# X7A15T-Fabric.net
KiCad netlist of a schematic drawn in Altium Designer
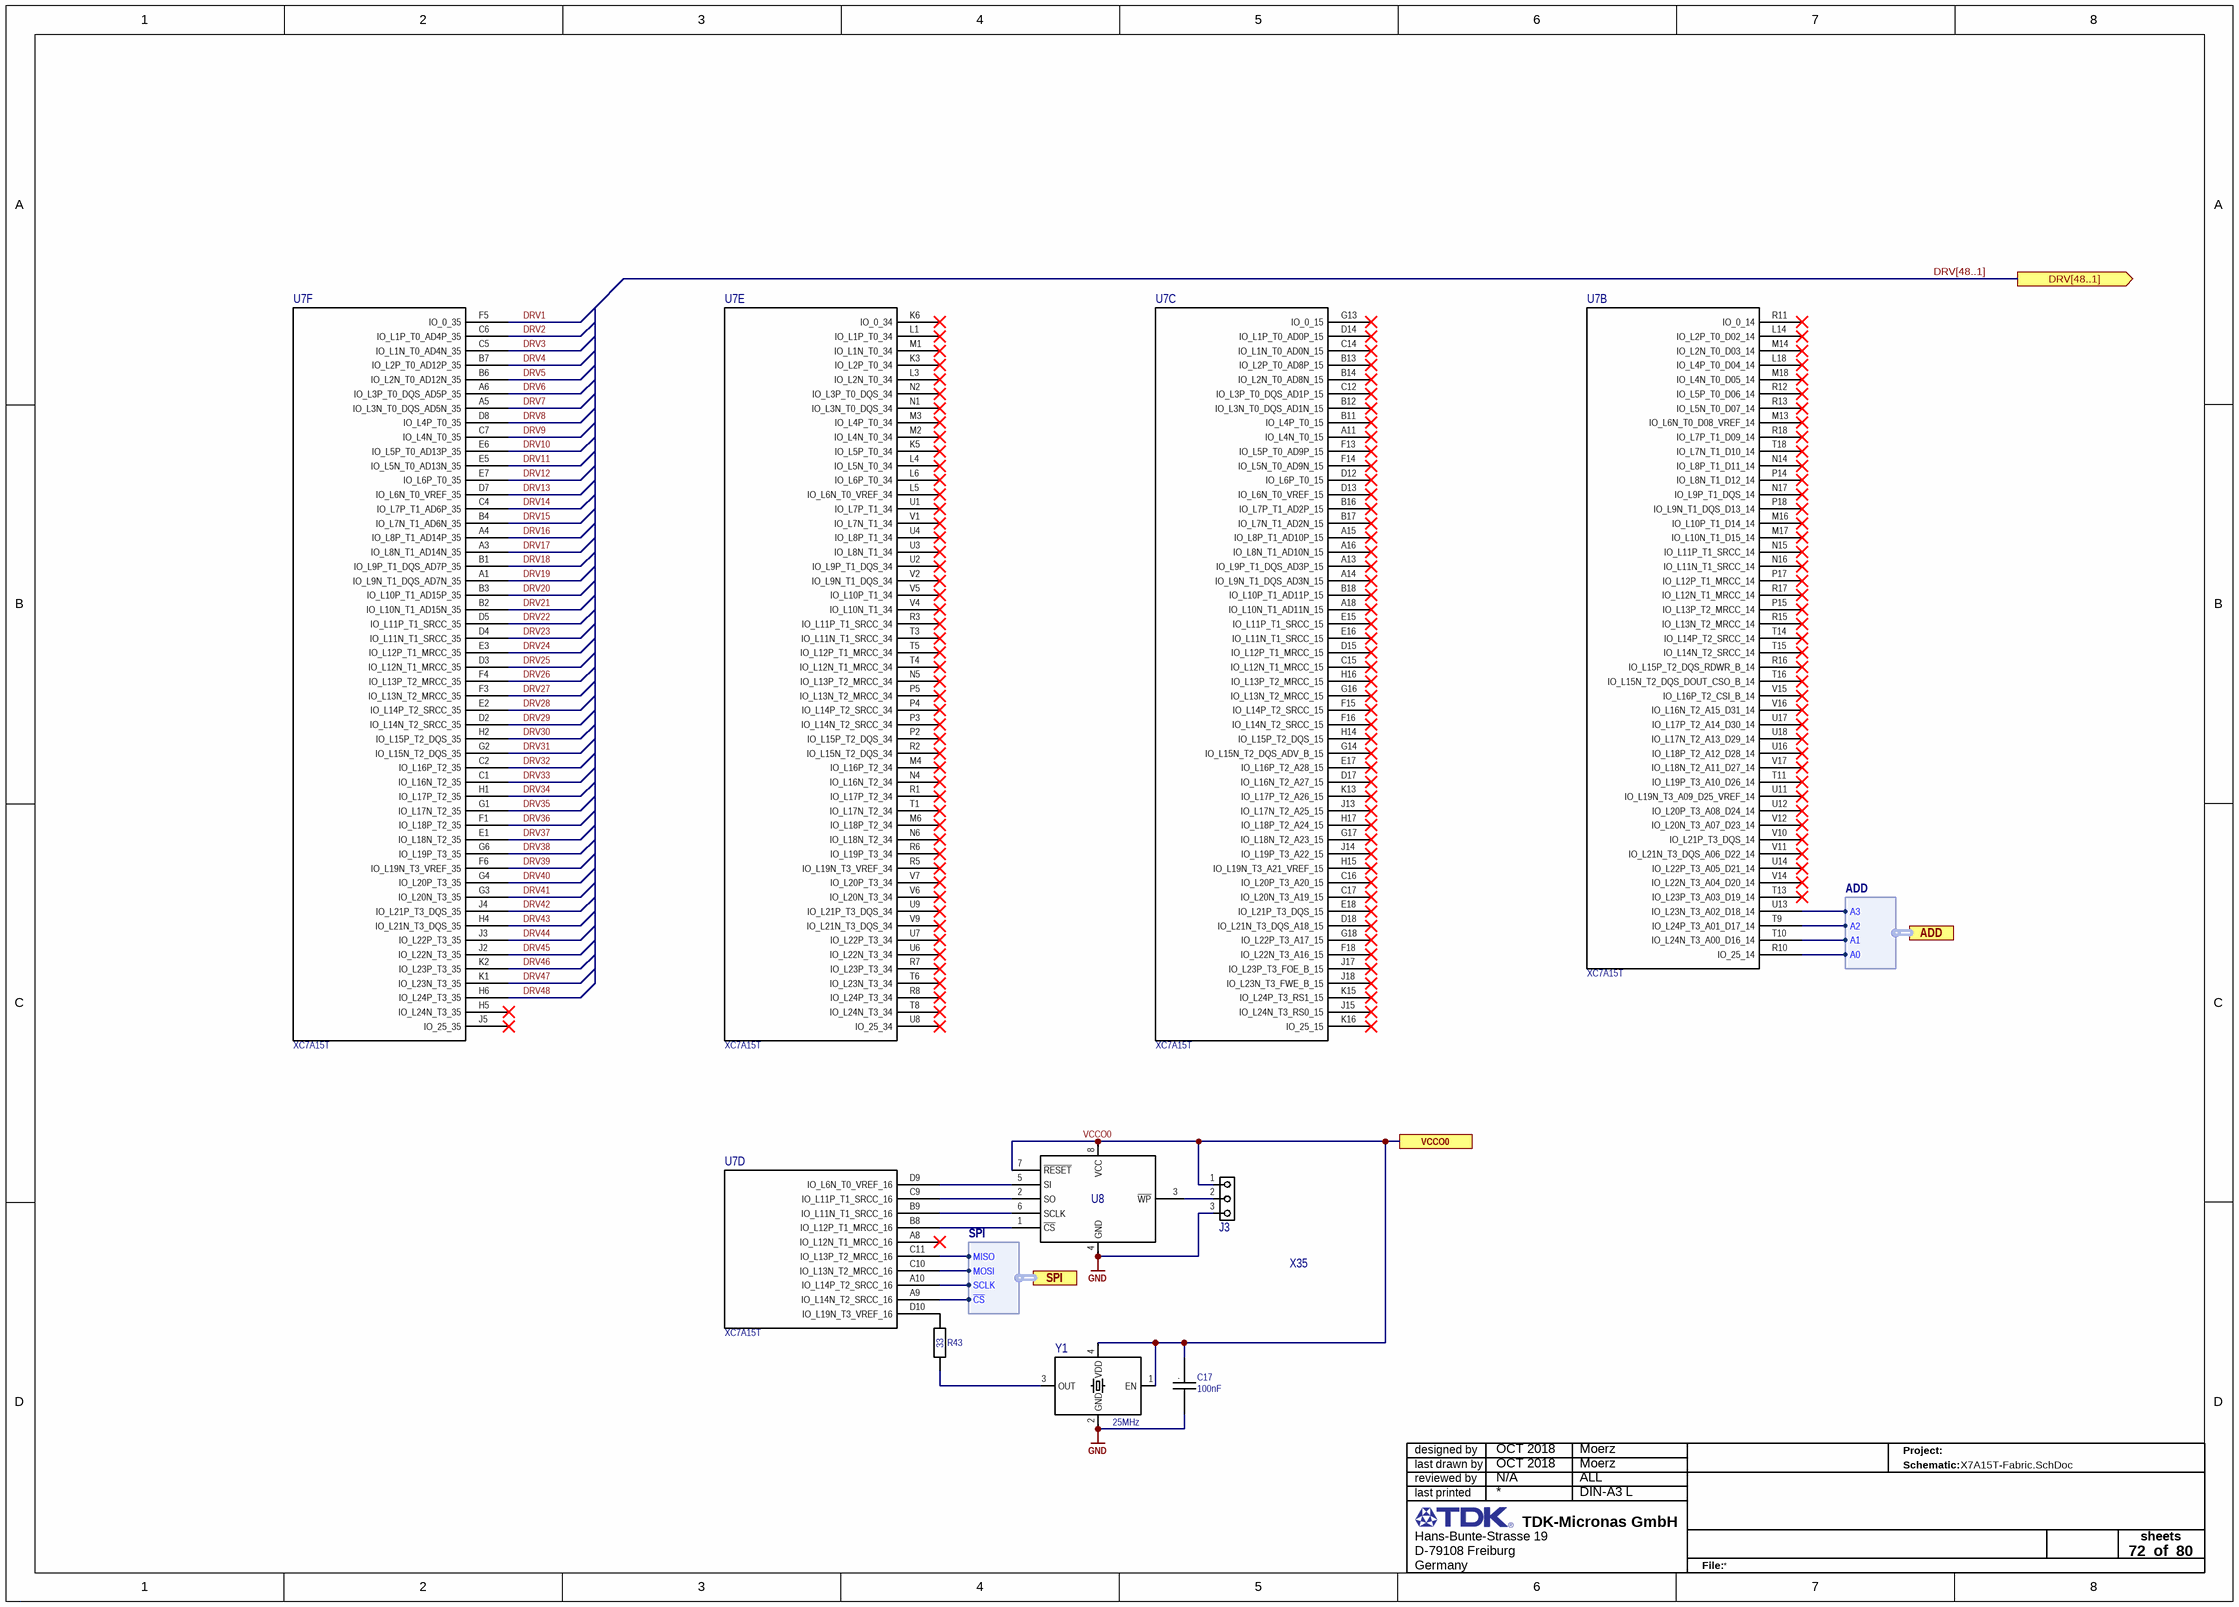
[diagram p0: X7A15T-Fabric.SchDoc]

(export (version "E")
  (design (tool "Eeschema 10.0.6"))
  (components
    (comp (ref "C17")
      (value "100nF")
      (footprint "C0402 Reflow")
      (description "CAP CER 0.1UF 16V X7R 0402")
      (fields
        (field (name "TOLERANCE") "±5%")
        (field (name "02. DISTRIBUTOR PART NUMBER") "399-7761-6-ND")
        (field (name "13. CREATED DATE/NAME") "AUG2018/Hören")
      )
      (libsource (lib "chickenfood") (part "C"))
    )
    (comp (ref "J3")
      (value "J")
      (footprint "Header 100mil 3x1")
      (description "CONN HEADER VERT 3POS 2.54MM")
      (fields
        (field (name "02. DISTRIBUTOR PART NUMBER") "HMTSW-103-07-G-S-240")
        (field (name "13. CREATED DATE/NAME") "AUG2018/Hören")
      )
      (libsource (lib "chickenfood") (part "Header 3Pins 100mil"))
    )
    (comp (ref "R43")
      (value "33")
      (footprint "R0402 Reflow")
      (description "RES SMD 33 OHM 1% 1/16W 0402")
      (fields
        (field (name "TOLERANCE") "±1%")
        (field (name "02. DISTRIBUTOR PART NUMBER") "311-33.0LRDKR-ND")
        (field (name "13. CREATED DATE/NAME") "AUG2018/Hören")
      )
      (libsource (lib "chickenfood") (part "R"))
    )
    (comp (ref "U7")
      (value "U")
      (footprint "XC7A15T-1CSG324C")
      (description "XC7A15T-1CSG324C")
      (fields (field (name "MFR") "XILINX") (field (name "NICNAME") "XC7A15T"))
      (libsource (lib "tom") (part "XC7A15T-CS324"))
    )
    (comp (ref "U8")
      (value "U")
      (footprint "SOIC8 (R-8)")
      (description "IC FLASH 32M SPI 80MHZ 8SOP")
      (fields (field (name "13. CREATED DATE/NAME") "AUG 2018 / Hören"))
      (libsource (lib "tom") (part "MX25R3235FM1IH0"))
    )
    (comp (ref "X35")
      (value "X")
      (description "CONN JUMPER SHORTING .100\" GOLD")
      (fields
        (field (name "02. DISTRIBUTOR PART NUMBER") "S9337-ND")
        (field (name "07. MANUFACTURER  PART NUMBER") "QPC02SXGN-RC")
        (field (name "13. CREATED DATE/NAME") "AUG2018/Hören")
      )
      (libsource (lib "chickenfood") (part "Jumper"))
    )
    (comp (ref "Y1")
      (value "Y")
      (footprint "4SMD")
      (description "XTAL OSC XO 25.0000MHZ CMOS SMD")
      (fields
        (field (name "02. DISTRIBUTOR PART NUMBER") "535-9568-1-ND")
        (field (name "07. MANUFACTURER  PART NUMBER") "ASE-25.000MHZ-LC-T")
        (field (name "FREQUENCY") "25MHz")
        (field (name "13. CREATED DATE/NAME") "AUG 2018 / Hören")
      )
      (libsource (lib "tom") (part "ASE-25.000MHZ-LC-T"))
    )
  )
  (nets
    (net (code "3") (name "/A0") (class "Default")
      (node (ref "U7") (pin "R10") (pinfunction "IO_25_14_R10") (pintype "passive"))
    )
    (net (code "4") (name "/A1") (class "Default")
      (node (ref "U7") (pin "T10") (pinfunction "IO_L24N_T3_A00_D16_14_T10") (pintype "passive"))
    )
    (net (code "5") (name "/A2") (class "Default")
      (node (ref "U7") (pin "T9") (pinfunction "IO_L24P_T3_A01_D17_14_T9") (pintype "passive"))
    )
    (net (code "6") (name "/A3") (class "Default")
      (node (ref "U7") (pin "U13") (pinfunction "IO_L23N_T3_A02_D18_14_U13") (pintype "passive"))
    )
    (net (code "7") (name "/DRV1") (class "Default")
      (node (ref "U7") (pin "F5") (pinfunction "IO_0_35_F5") (pintype "passive"))
    )
    (net (code "8") (name "/DRV2") (class "Default")
      (node (ref "U7") (pin "C6") (pinfunction "IO_L1P_T0_AD4P_35_C6") (pintype "passive"))
    )
    (net (code "9") (name "/DRV3") (class "Default")
      (node (ref "U7") (pin "C5") (pinfunction "IO_L1N_T0_AD4N_35_C5") (pintype "passive"))
    )
    (net (code "10") (name "/DRV4") (class "Default")
      (node (ref "U7") (pin "B7") (pinfunction "IO_L2P_T0_AD12P_35_B7") (pintype "passive"))
    )
    (net (code "11") (name "/DRV5") (class "Default")
      (node (ref "U7") (pin "B6") (pinfunction "IO_L2N_T0_AD12N_35_B6") (pintype "passive"))
    )
    (net (code "12") (name "/DRV6") (class "Default")
      (node (ref "U7") (pin "A6") (pinfunction "IO_L3P_T0_DQS_AD5P_35_A6") (pintype "passive"))
    )
    (net (code "13") (name "/DRV7") (class "Default")
      (node (ref "U7") (pin "A5") (pinfunction "IO_L3N_T0_DQS_AD5N_35_A5") (pintype "passive"))
    )
    (net (code "14") (name "/DRV8") (class "Default")
      (node (ref "U7") (pin "D8") (pinfunction "IO_L4P_T0_35_D8") (pintype "passive"))
    )
    (net (code "15") (name "/DRV9") (class "Default")
      (node (ref "U7") (pin "C7") (pinfunction "IO_L4N_T0_35_C7") (pintype "passive"))
    )
    (net (code "16") (name "/DRV10") (class "Default")
      (node (ref "U7") (pin "E6") (pinfunction "IO_L5P_T0_AD13P_35_E6") (pintype "passive"))
    )
    (net (code "17") (name "/DRV11") (class "Default")
      (node (ref "U7") (pin "E5") (pinfunction "IO_L5N_T0_AD13N_35_E5") (pintype "passive"))
    )
    (net (code "18") (name "/DRV12") (class "Default")
      (node (ref "U7") (pin "E7") (pinfunction "IO_L6P_T0_35_E7") (pintype "passive"))
    )
    (net (code "19") (name "/DRV13") (class "Default")
      (node (ref "U7") (pin "D7") (pinfunction "IO_L6N_T0_VREF_35_D7") (pintype "passive"))
    )
    (net (code "20") (name "/DRV14") (class "Default")
      (node (ref "U7") (pin "C4") (pinfunction "IO_L7P_T1_AD6P_35_C4") (pintype "passive"))
    )
    (net (code "21") (name "/DRV15") (class "Default")
      (node (ref "U7") (pin "B4") (pinfunction "IO_L7N_T1_AD6N_35_B4") (pintype "passive"))
    )
    (net (code "22") (name "/DRV16") (class "Default")
      (node (ref "U7") (pin "A4") (pinfunction "IO_L8P_T1_AD14P_35_A4") (pintype "passive"))
    )
    (net (code "23") (name "/DRV17") (class "Default")
      (node (ref "U7") (pin "A3") (pinfunction "IO_L8N_T1_AD14N_35_A3") (pintype "passive"))
    )
    (net (code "24") (name "/DRV18") (class "Default")
      (node (ref "U7") (pin "B1") (pinfunction "IO_L9P_T1_DQS_AD7P_35_B1") (pintype "passive"))
    )
    (net (code "25") (name "/DRV19") (class "Default")
      (node (ref "U7") (pin "A1") (pinfunction "IO_L9N_T1_DQS_AD7N_35_A1") (pintype "passive"))
    )
    (net (code "26") (name "/DRV20") (class "Default")
      (node (ref "U7") (pin "B3") (pinfunction "IO_L10P_T1_AD15P_35_B3") (pintype "passive"))
    )
    (net (code "27") (name "/DRV21") (class "Default")
      (node (ref "U7") (pin "B2") (pinfunction "IO_L10N_T1_AD15N_35_B2") (pintype "passive"))
    )
    (net (code "28") (name "/DRV22") (class "Default")
      (node (ref "U7") (pin "D5") (pinfunction "IO_L11P_T1_SRCC_35_D5") (pintype "passive"))
    )
    (net (code "29") (name "/DRV23") (class "Default")
      (node (ref "U7") (pin "D4") (pinfunction "IO_L11N_T1_SRCC_35_D4") (pintype "passive"))
    )
    (net (code "30") (name "/DRV24") (class "Default")
      (node (ref "U7") (pin "E3") (pinfunction "IO_L12P_T1_MRCC_35_E3") (pintype "passive"))
    )
    (net (code "31") (name "/DRV25") (class "Default")
      (node (ref "U7") (pin "D3") (pinfunction "IO_L12N_T1_MRCC_35_D3") (pintype "passive"))
    )
    (net (code "32") (name "/DRV26") (class "Default")
      (node (ref "U7") (pin "F4") (pinfunction "IO_L13P_T2_MRCC_35_F4") (pintype "passive"))
    )
    (net (code "33") (name "/DRV27") (class "Default")
      (node (ref "U7") (pin "F3") (pinfunction "IO_L13N_T2_MRCC_35_F3") (pintype "passive"))
    )
    (net (code "34") (name "/DRV28") (class "Default")
      (node (ref "U7") (pin "E2") (pinfunction "IO_L14P_T2_SRCC_35_E2") (pintype "passive"))
    )
    (net (code "35") (name "/DRV29") (class "Default")
      (node (ref "U7") (pin "D2") (pinfunction "IO_L14N_T2_SRCC_35_D2") (pintype "passive"))
    )
    (net (code "36") (name "/DRV30") (class "Default")
      (node (ref "U7") (pin "H2") (pinfunction "IO_L15P_T2_DQS_35_H2") (pintype "passive"))
    )
    (net (code "37") (name "/DRV31") (class "Default")
      (node (ref "U7") (pin "G2") (pinfunction "IO_L15N_T2_DQS_35_G2") (pintype "passive"))
    )
    (net (code "38") (name "/DRV32") (class "Default")
      (node (ref "U7") (pin "C2") (pinfunction "IO_L16P_T2_35_C2") (pintype "passive"))
    )
    (net (code "39") (name "/DRV33") (class "Default")
      (node (ref "U7") (pin "C1") (pinfunction "IO_L16N_T2_35_C1") (pintype "passive"))
    )
    (net (code "40") (name "/DRV34") (class "Default")
      (node (ref "U7") (pin "H1") (pinfunction "IO_L17P_T2_35_H1") (pintype "passive"))
    )
    (net (code "41") (name "/DRV35") (class "Default")
      (node (ref "U7") (pin "G1") (pinfunction "IO_L17N_T2_35_G1") (pintype "passive"))
    )
    (net (code "42") (name "/DRV36") (class "Default")
      (node (ref "U7") (pin "F1") (pinfunction "IO_L18P_T2_35_F1") (pintype "passive"))
    )
    (net (code "43") (name "/DRV37") (class "Default")
      (node (ref "U7") (pin "E1") (pinfunction "IO_L18N_T2_35_E1") (pintype "passive"))
    )
    (net (code "44") (name "/DRV38") (class "Default")
      (node (ref "U7") (pin "G6") (pinfunction "IO_L19P_T3_35_G6") (pintype "passive"))
    )
    (net (code "45") (name "/DRV39") (class "Default")
      (node (ref "U7") (pin "F6") (pinfunction "IO_L19N_T3_VREF_35_F6") (pintype "passive"))
    )
    (net (code "46") (name "/DRV40") (class "Default")
      (node (ref "U7") (pin "G4") (pinfunction "IO_L20P_T3_35_G4") (pintype "passive"))
    )
    (net (code "47") (name "/DRV41") (class "Default")
      (node (ref "U7") (pin "G3") (pinfunction "IO_L20N_T3_35_G3") (pintype "passive"))
    )
    (net (code "48") (name "/DRV42") (class "Default")
      (node (ref "U7") (pin "J4") (pinfunction "IO_L21P_T3_DQS_35_J4") (pintype "passive"))
    )
    (net (code "49") (name "/DRV43") (class "Default")
      (node (ref "U7") (pin "H4") (pinfunction "IO_L21N_T3_DQS_35_H4") (pintype "passive"))
    )
    (net (code "50") (name "/DRV44") (class "Default")
      (node (ref "U7") (pin "J3") (pinfunction "IO_L22P_T3_35_J3") (pintype "passive"))
    )
    (net (code "51") (name "/DRV45") (class "Default")
      (node (ref "U7") (pin "J2") (pinfunction "IO_L22N_T3_35_J2") (pintype "passive"))
    )
    (net (code "52") (name "/DRV46") (class "Default")
      (node (ref "U7") (pin "K2") (pinfunction "IO_L23P_T3_35_K2") (pintype "passive"))
    )
    (net (code "53") (name "/DRV47") (class "Default")
      (node (ref "U7") (pin "K1") (pinfunction "IO_L23N_T3_35_K1") (pintype "passive"))
    )
    (net (code "54") (name "/DRV48") (class "Default")
      (node (ref "U7") (pin "H6") (pinfunction "IO_L24P_T3_35_H6") (pintype "passive"))
    )
    (net (code "56") (name "/MISO") (class "Default")
      (node (ref "U7") (pin "C11") (pinfunction "IO_L13P_T2_MRCC_16_C11") (pintype "passive"))
    )
    (net (code "57") (name "/MOSI") (class "Default")
      (node (ref "U7") (pin "C10") (pinfunction "IO_L13N_T2_MRCC_16_C10") (pintype "passive"))
    )
    (net (code "58") (name "/SCLK") (class "Default")
      (node (ref "U7") (pin "A10") (pinfunction "IO_L14P_T2_SRCC_16_A10") (pintype "passive"))
    )
    (net (code "59") (name "/VCCO0") (class "Default")
      (node (ref "C17") (pin "1") (pinfunction "1_1") (pintype "passive"))
      (node (ref "J3") (pin "1") (pinfunction "1_1") (pintype "passive"))
      (node (ref "U8") (pin "7") (pinfunction "RESET_7") (pintype "passive"))
      (node (ref "U8") (pin "8") (pinfunction "VCC_8") (pintype "passive"))
      (node (ref "Y1") (pin "1") (pinfunction "EN_1") (pintype "passive"))
      (node (ref "Y1") (pin "4") (pinfunction "VDD_4") (pintype "passive"))
    )
    (net (code "62") (name "/~{CS}") (class "Default")
      (node (ref "U7") (pin "A9") (pinfunction "IO_L14N_T2_SRCC_16_A9") (pintype "passive"))
    )
    (net (code "63") (name "GND") (class "Default")
      (node (ref "C17") (pin "2") (pinfunction "2_2") (pintype "passive"))
      (node (ref "J3") (pin "3") (pinfunction "3_3") (pintype "passive"))
      (node (ref "U8") (pin "4") (pinfunction "GND_4") (pintype "passive"))
      (node (ref "Y1") (pin "2") (pinfunction "GND_2") (pintype "passive"))
    )
    (net (code "64") (name "Net-(U7D-IO_L6N_T0_VREF_16)") (class "Default")
      (node (ref "U7") (pin "D9") (pinfunction "IO_L6N_T0_VREF_16_D9") (pintype "passive"))
      (node (ref "U8") (pin "5") (pinfunction "SI_5") (pintype "passive"))
    )
    (net (code "65") (name "Net-(U7D-IO_L11N_T1_SRCC_16)") (class "Default")
      (node (ref "U7") (pin "B9") (pinfunction "IO_L11N_T1_SRCC_16_B9") (pintype "passive"))
      (node (ref "U8") (pin "6") (pinfunction "SCLK_6") (pintype "passive"))
    )
    (net (code "66") (name "Net-(U7D-IO_L11P_T1_SRCC_16)") (class "Default")
      (node (ref "U7") (pin "C9") (pinfunction "IO_L11P_T1_SRCC_16_C9") (pintype "passive"))
      (node (ref "U8") (pin "2") (pinfunction "SO_2") (pintype "passive"))
    )
    (net (code "67") (name "Net-(U7D-IO_L12P_T1_MRCC_16)") (class "Default")
      (node (ref "U7") (pin "B8") (pinfunction "IO_L12P_T1_MRCC_16_B8") (pintype "passive"))
      (node (ref "U8") (pin "1") (pinfunction "CS_1") (pintype "passive"))
    )
    (net (code "68") (name "Net-(U7D-IO_L19N_T3_VREF_16)") (class "Default")
      (node (ref "R43") (pin "2") (pinfunction "2_2") (pintype "passive"))
      (node (ref "U7") (pin "D10") (pinfunction "IO_L19N_T3_VREF_16_D10") (pintype "passive"))
    )
    (net (code "69") (name "Net-(U8-WP)") (class "Default")
      (node (ref "J3") (pin "2") (pinfunction "2_2") (pintype "passive"))
      (node (ref "U8") (pin "3") (pinfunction "WP_3") (pintype "passive"))
    )
    (net (code "70") (name "Net-(Y1-OUT)") (class "Default")
      (node (ref "R43") (pin "1") (pinfunction "1_1") (pintype "passive"))
      (node (ref "Y1") (pin "3") (pinfunction "OUT_3") (pintype "passive"))
    )
    (net (code "71") (name "unconnected-(U7B-IO_0_14-PadR11)") (class "Default")
      (node (ref "U7") (pin "R11") (pinfunction "IO_0_14_R11") (pintype "passive+no_connect"))
    )
    (net (code "72") (name "unconnected-(U7B-IO_L2N_T0_D03_14-PadM14)") (class "Default")
      (node (ref "U7") (pin "M14") (pinfunction "IO_L2N_T0_D03_14_M14") (pintype "passive+no_connect"))
    )
    (net (code "73") (name "unconnected-(U7B-IO_L2P_T0_D02_14-PadL14)") (class "Default")
      (node (ref "U7") (pin "L14") (pinfunction "IO_L2P_T0_D02_14_L14") (pintype "passive+no_connect"))
    )
    (net (code "74") (name "unconnected-(U7B-IO_L4N_T0_D05_14-PadM18)") (class "Default")
      (node (ref "U7") (pin "M18") (pinfunction "IO_L4N_T0_D05_14_M18") (pintype "passive+no_connect"))
    )
    (net (code "75") (name "unconnected-(U7B-IO_L4P_T0_D04_14-PadL18)") (class "Default")
      (node (ref "U7") (pin "L18") (pinfunction "IO_L4P_T0_D04_14_L18") (pintype "passive+no_connect"))
    )
    (net (code "76") (name "unconnected-(U7B-IO_L5N_T0_D07_14-PadR13)") (class "Default")
      (node (ref "U7") (pin "R13") (pinfunction "IO_L5N_T0_D07_14_R13") (pintype "passive+no_connect"))
    )
    (net (code "77") (name "unconnected-(U7B-IO_L5P_T0_D06_14-PadR12)") (class "Default")
      (node (ref "U7") (pin "R12") (pinfunction "IO_L5P_T0_D06_14_R12") (pintype "passive+no_connect"))
    )
    (net (code "78") (name "unconnected-(U7B-IO_L6N_T0_D08_VREF_14-PadM13)") (class "Default")
      (node (ref "U7") (pin "M13") (pinfunction "IO_L6N_T0_D08_VREF_14_M13") (pintype "passive+no_connect"))
    )
    (net (code "79") (name "unconnected-(U7B-IO_L7N_T1_D10_14-PadT18)") (class "Default")
      (node (ref "U7") (pin "T18") (pinfunction "IO_L7N_T1_D10_14_T18") (pintype "passive+no_connect"))
    )
    (net (code "80") (name "unconnected-(U7B-IO_L7P_T1_D09_14-PadR18)") (class "Default")
      (node (ref "U7") (pin "R18") (pinfunction "IO_L7P_T1_D09_14_R18") (pintype "passive+no_connect"))
    )
    (net (code "81") (name "unconnected-(U7B-IO_L8N_T1_D12_14-PadP14)") (class "Default")
      (node (ref "U7") (pin "P14") (pinfunction "IO_L8N_T1_D12_14_P14") (pintype "passive+no_connect"))
    )
    (net (code "82") (name "unconnected-(U7B-IO_L8P_T1_D11_14-PadN14)") (class "Default")
      (node (ref "U7") (pin "N14") (pinfunction "IO_L8P_T1_D11_14_N14") (pintype "passive+no_connect"))
    )
    (net (code "83") (name "unconnected-(U7B-IO_L9N_T1_DQS_D13_14-PadP18)") (class "Default")
      (node (ref "U7") (pin "P18") (pinfunction "IO_L9N_T1_DQS_D13_14_P18") (pintype "passive+no_connect"))
    )
    (net (code "84") (name "unconnected-(U7B-IO_L9P_T1_DQS_14-PadN17)") (class "Default")
      (node (ref "U7") (pin "N17") (pinfunction "IO_L9P_T1_DQS_14_N17") (pintype "passive+no_connect"))
    )
    (net (code "85") (name "unconnected-(U7B-IO_L10N_T1_D15_14-PadM17)") (class "Default")
      (node (ref "U7") (pin "M17") (pinfunction "IO_L10N_T1_D15_14_M17") (pintype "passive+no_connect"))
    )
    (net (code "86") (name "unconnected-(U7B-IO_L10P_T1_D14_14-PadM16)") (class "Default")
      (node (ref "U7") (pin "M16") (pinfunction "IO_L10P_T1_D14_14_M16") (pintype "passive+no_connect"))
    )
    (net (code "87") (name "unconnected-(U7B-IO_L11N_T1_SRCC_14-PadN16)") (class "Default")
      (node (ref "U7") (pin "N16") (pinfunction "IO_L11N_T1_SRCC_14_N16") (pintype "passive+no_connect"))
    )
    (net (code "88") (name "unconnected-(U7B-IO_L11P_T1_SRCC_14-PadN15)") (class "Default")
      (node (ref "U7") (pin "N15") (pinfunction "IO_L11P_T1_SRCC_14_N15") (pintype "passive+no_connect"))
    )
    (net (code "89") (name "unconnected-(U7B-IO_L12N_T1_MRCC_14-PadR17)") (class "Default")
      (node (ref "U7") (pin "R17") (pinfunction "IO_L12N_T1_MRCC_14_R17") (pintype "passive+no_connect"))
    )
    (net (code "90") (name "unconnected-(U7B-IO_L12P_T1_MRCC_14-PadP17)") (class "Default")
      (node (ref "U7") (pin "P17") (pinfunction "IO_L12P_T1_MRCC_14_P17") (pintype "passive+no_connect"))
    )
    (net (code "91") (name "unconnected-(U7B-IO_L13N_T2_MRCC_14-PadR15)") (class "Default")
      (node (ref "U7") (pin "R15") (pinfunction "IO_L13N_T2_MRCC_14_R15") (pintype "passive+no_connect"))
    )
    (net (code "92") (name "unconnected-(U7B-IO_L13P_T2_MRCC_14-PadP15)") (class "Default")
      (node (ref "U7") (pin "P15") (pinfunction "IO_L13P_T2_MRCC_14_P15") (pintype "passive+no_connect"))
    )
    (net (code "93") (name "unconnected-(U7B-IO_L14N_T2_SRCC_14-PadT15)") (class "Default")
      (node (ref "U7") (pin "T15") (pinfunction "IO_L14N_T2_SRCC_14_T15") (pintype "passive+no_connect"))
    )
    (net (code "94") (name "unconnected-(U7B-IO_L14P_T2_SRCC_14-PadT14)") (class "Default")
      (node (ref "U7") (pin "T14") (pinfunction "IO_L14P_T2_SRCC_14_T14") (pintype "passive+no_connect"))
    )
    (net (code "95") (name "unconnected-(U7B-IO_L15N_T2_DQS_DOUT_CSO_B_14-PadT16)") (class "Default")
      (node (ref "U7") (pin "T16") (pinfunction "IO_L15N_T2_DQS_DOUT_CSO_B_14_T16") (pintype "passive+no_connect"))
    )
    (net (code "96") (name "unconnected-(U7B-IO_L15P_T2_DQS_RDWR_B_14-PadR16)") (class "Default")
      (node (ref "U7") (pin "R16") (pinfunction "IO_L15P_T2_DQS_RDWR_B_14_R16") (pintype "passive+no_connect"))
    )
    (net (code "97") (name "unconnected-(U7B-IO_L16N_T2_A15_D31_14-PadV16)") (class "Default")
      (node (ref "U7") (pin "V16") (pinfunction "IO_L16N_T2_A15_D31_14_V16") (pintype "passive+no_connect"))
    )
    (net (code "98") (name "unconnected-(U7B-IO_L16P_T2_CSI_B_14-PadV15)") (class "Default")
      (node (ref "U7") (pin "V15") (pinfunction "IO_L16P_T2_CSI_B_14_V15") (pintype "passive+no_connect"))
    )
    (net (code "99") (name "unconnected-(U7B-IO_L17N_T2_A13_D29_14-PadU18)") (class "Default")
      (node (ref "U7") (pin "U18") (pinfunction "IO_L17N_T2_A13_D29_14_U18") (pintype "passive+no_connect"))
    )
    (net (code "100") (name "unconnected-(U7B-IO_L17P_T2_A14_D30_14-PadU17)") (class "Default")
      (node (ref "U7") (pin "U17") (pinfunction "IO_L17P_T2_A14_D30_14_U17") (pintype "passive+no_connect"))
    )
    (net (code "101") (name "unconnected-(U7B-IO_L18N_T2_A11_D27_14-PadV17)") (class "Default")
      (node (ref "U7") (pin "V17") (pinfunction "IO_L18N_T2_A11_D27_14_V17") (pintype "passive+no_connect"))
    )
    (net (code "102") (name "unconnected-(U7B-IO_L18P_T2_A12_D28_14-PadU16)") (class "Default")
      (node (ref "U7") (pin "U16") (pinfunction "IO_L18P_T2_A12_D28_14_U16") (pintype "passive+no_connect"))
    )
    (net (code "103") (name "unconnected-(U7B-IO_L19N_T3_A09_D25_VREF_14-PadU11)") (class "Default")
      (node (ref "U7") (pin "U11") (pinfunction "IO_L19N_T3_A09_D25_VREF_14_U11") (pintype "passive+no_connect"))
    )
    (net (code "104") (name "unconnected-(U7B-IO_L19P_T3_A10_D26_14-PadT11)") (class "Default")
      (node (ref "U7") (pin "T11") (pinfunction "IO_L19P_T3_A10_D26_14_T11") (pintype "passive+no_connect"))
    )
    (net (code "105") (name "unconnected-(U7B-IO_L20N_T3_A07_D23_14-PadV12)") (class "Default")
      (node (ref "U7") (pin "V12") (pinfunction "IO_L20N_T3_A07_D23_14_V12") (pintype "passive+no_connect"))
    )
    (net (code "106") (name "unconnected-(U7B-IO_L20P_T3_A08_D24_14-PadU12)") (class "Default")
      (node (ref "U7") (pin "U12") (pinfunction "IO_L20P_T3_A08_D24_14_U12") (pintype "passive+no_connect"))
    )
    (net (code "107") (name "unconnected-(U7B-IO_L21N_T3_DQS_A06_D22_14-PadV11)") (class "Default")
      (node (ref "U7") (pin "V11") (pinfunction "IO_L21N_T3_DQS_A06_D22_14_V11") (pintype "passive+no_connect"))
    )
    (net (code "108") (name "unconnected-(U7B-IO_L21P_T3_DQS_14-PadV10)") (class "Default")
      (node (ref "U7") (pin "V10") (pinfunction "IO_L21P_T3_DQS_14_V10") (pintype "passive+no_connect"))
    )
    (net (code "109") (name "unconnected-(U7B-IO_L22N_T3_A04_D20_14-PadV14)") (class "Default")
      (node (ref "U7") (pin "V14") (pinfunction "IO_L22N_T3_A04_D20_14_V14") (pintype "passive+no_connect"))
    )
    (net (code "110") (name "unconnected-(U7B-IO_L22P_T3_A05_D21_14-PadU14)") (class "Default")
      (node (ref "U7") (pin "U14") (pinfunction "IO_L22P_T3_A05_D21_14_U14") (pintype "passive+no_connect"))
    )
    (net (code "111") (name "unconnected-(U7B-IO_L23P_T3_A03_D19_14-PadT13)") (class "Default")
      (node (ref "U7") (pin "T13") (pinfunction "IO_L23P_T3_A03_D19_14_T13") (pintype "passive+no_connect"))
    )
    (net (code "112") (name "unconnected-(U7C-IO_0_15-PadG13)") (class "Default")
      (node (ref "U7") (pin "G13") (pinfunction "IO_0_15_G13") (pintype "passive+no_connect"))
    )
    (net (code "113") (name "unconnected-(U7C-IO_25_15-PadK16)") (class "Default")
      (node (ref "U7") (pin "K16") (pinfunction "IO_25_15_K16") (pintype "passive+no_connect"))
    )
    (net (code "114") (name "unconnected-(U7C-IO_L1N_T0_AD0N_15-PadC14)") (class "Default")
      (node (ref "U7") (pin "C14") (pinfunction "IO_L1N_T0_AD0N_15_C14") (pintype "passive+no_connect"))
    )
    (net (code "115") (name "unconnected-(U7C-IO_L1P_T0_AD0P_15-PadD14)") (class "Default")
      (node (ref "U7") (pin "D14") (pinfunction "IO_L1P_T0_AD0P_15_D14") (pintype "passive+no_connect"))
    )
    (net (code "116") (name "unconnected-(U7C-IO_L2N_T0_AD8N_15-PadB14)") (class "Default")
      (node (ref "U7") (pin "B14") (pinfunction "IO_L2N_T0_AD8N_15_B14") (pintype "passive+no_connect"))
    )
    (net (code "117") (name "unconnected-(U7C-IO_L2P_T0_AD8P_15-PadB13)") (class "Default")
      (node (ref "U7") (pin "B13") (pinfunction "IO_L2P_T0_AD8P_15_B13") (pintype "passive+no_connect"))
    )
    (net (code "118") (name "unconnected-(U7C-IO_L3N_T0_DQS_AD1N_15-PadB12)") (class "Default")
      (node (ref "U7") (pin "B12") (pinfunction "IO_L3N_T0_DQS_AD1N_15_B12") (pintype "passive+no_connect"))
    )
    (net (code "119") (name "unconnected-(U7C-IO_L3P_T0_DQS_AD1P_15-PadC12)") (class "Default")
      (node (ref "U7") (pin "C12") (pinfunction "IO_L3P_T0_DQS_AD1P_15_C12") (pintype "passive+no_connect"))
    )
    (net (code "120") (name "unconnected-(U7C-IO_L4N_T0_15-PadA11)") (class "Default")
      (node (ref "U7") (pin "A11") (pinfunction "IO_L4N_T0_15_A11") (pintype "passive+no_connect"))
    )
    (net (code "121") (name "unconnected-(U7C-IO_L4P_T0_15-PadB11)") (class "Default")
      (node (ref "U7") (pin "B11") (pinfunction "IO_L4P_T0_15_B11") (pintype "passive+no_connect"))
    )
    (net (code "122") (name "unconnected-(U7C-IO_L5N_T0_AD9N_15-PadF14)") (class "Default")
      (node (ref "U7") (pin "F14") (pinfunction "IO_L5N_T0_AD9N_15_F14") (pintype "passive+no_connect"))
    )
    (net (code "123") (name "unconnected-(U7C-IO_L5P_T0_AD9P_15-PadF13)") (class "Default")
      (node (ref "U7") (pin "F13") (pinfunction "IO_L5P_T0_AD9P_15_F13") (pintype "passive+no_connect"))
    )
    (net (code "124") (name "unconnected-(U7C-IO_L6N_T0_VREF_15-PadD13)") (class "Default")
      (node (ref "U7") (pin "D13") (pinfunction "IO_L6N_T0_VREF_15_D13") (pintype "passive+no_connect"))
    )
    (net (code "125") (name "unconnected-(U7C-IO_L6P_T0_15-PadD12)") (class "Default")
      (node (ref "U7") (pin "D12") (pinfunction "IO_L6P_T0_15_D12") (pintype "passive+no_connect"))
    )
    (net (code "126") (name "unconnected-(U7C-IO_L7N_T1_AD2N_15-PadB17)") (class "Default")
      (node (ref "U7") (pin "B17") (pinfunction "IO_L7N_T1_AD2N_15_B17") (pintype "passive+no_connect"))
    )
    (net (code "127") (name "unconnected-(U7C-IO_L7P_T1_AD2P_15-PadB16)") (class "Default")
      (node (ref "U7") (pin "B16") (pinfunction "IO_L7P_T1_AD2P_15_B16") (pintype "passive+no_connect"))
    )
    (net (code "128") (name "unconnected-(U7C-IO_L8N_T1_AD10N_15-PadA16)") (class "Default")
      (node (ref "U7") (pin "A16") (pinfunction "IO_L8N_T1_AD10N_15_A16") (pintype "passive+no_connect"))
    )
    (net (code "129") (name "unconnected-(U7C-IO_L8P_T1_AD10P_15-PadA15)") (class "Default")
      (node (ref "U7") (pin "A15") (pinfunction "IO_L8P_T1_AD10P_15_A15") (pintype "passive+no_connect"))
    )
    (net (code "130") (name "unconnected-(U7C-IO_L9N_T1_DQS_AD3N_15-PadA14)") (class "Default")
      (node (ref "U7") (pin "A14") (pinfunction "IO_L9N_T1_DQS_AD3N_15_A14") (pintype "passive+no_connect"))
    )
    (net (code "131") (name "unconnected-(U7C-IO_L9P_T1_DQS_AD3P_15-PadA13)") (class "Default")
      (node (ref "U7") (pin "A13") (pinfunction "IO_L9P_T1_DQS_AD3P_15_A13") (pintype "passive+no_connect"))
    )
    (net (code "132") (name "unconnected-(U7C-IO_L10N_T1_AD11N_15-PadA18)") (class "Default")
      (node (ref "U7") (pin "A18") (pinfunction "IO_L10N_T1_AD11N_15_A18") (pintype "passive+no_connect"))
    )
    (net (code "133") (name "unconnected-(U7C-IO_L10P_T1_AD11P_15-PadB18)") (class "Default")
      (node (ref "U7") (pin "B18") (pinfunction "IO_L10P_T1_AD11P_15_B18") (pintype "passive+no_connect"))
    )
    (net (code "134") (name "unconnected-(U7C-IO_L11N_T1_SRCC_15-PadE16)") (class "Default")
      (node (ref "U7") (pin "E16") (pinfunction "IO_L11N_T1_SRCC_15_E16") (pintype "passive+no_connect"))
    )
    (net (code "135") (name "unconnected-(U7C-IO_L11P_T1_SRCC_15-PadE15)") (class "Default")
      (node (ref "U7") (pin "E15") (pinfunction "IO_L11P_T1_SRCC_15_E15") (pintype "passive+no_connect"))
    )
    (net (code "136") (name "unconnected-(U7C-IO_L12N_T1_MRCC_15-PadC15)") (class "Default")
      (node (ref "U7") (pin "C15") (pinfunction "IO_L12N_T1_MRCC_15_C15") (pintype "passive+no_connect"))
    )
    (net (code "137") (name "unconnected-(U7C-IO_L12P_T1_MRCC_15-PadD15)") (class "Default")
      (node (ref "U7") (pin "D15") (pinfunction "IO_L12P_T1_MRCC_15_D15") (pintype "passive+no_connect"))
    )
    (net (code "138") (name "unconnected-(U7C-IO_L13N_T2_MRCC_15-PadG16)") (class "Default")
      (node (ref "U7") (pin "G16") (pinfunction "IO_L13N_T2_MRCC_15_G16") (pintype "passive+no_connect"))
    )
    (net (code "139") (name "unconnected-(U7C-IO_L13P_T2_MRCC_15-PadH16)") (class "Default")
      (node (ref "U7") (pin "H16") (pinfunction "IO_L13P_T2_MRCC_15_H16") (pintype "passive+no_connect"))
    )
    (net (code "140") (name "unconnected-(U7C-IO_L14N_T2_SRCC_15-PadF16)") (class "Default")
      (node (ref "U7") (pin "F16") (pinfunction "IO_L14N_T2_SRCC_15_F16") (pintype "passive+no_connect"))
    )
    (net (code "141") (name "unconnected-(U7C-IO_L14P_T2_SRCC_15-PadF15)") (class "Default")
      (node (ref "U7") (pin "F15") (pinfunction "IO_L14P_T2_SRCC_15_F15") (pintype "passive+no_connect"))
    )
    (net (code "142") (name "unconnected-(U7C-IO_L15N_T2_DQS_ADV_B_15-PadG14)") (class "Default")
      (node (ref "U7") (pin "G14") (pinfunction "IO_L15N_T2_DQS_ADV_B_15_G14") (pintype "passive+no_connect"))
    )
    (net (code "143") (name "unconnected-(U7C-IO_L15P_T2_DQS_15-PadH14)") (class "Default")
      (node (ref "U7") (pin "H14") (pinfunction "IO_L15P_T2_DQS_15_H14") (pintype "passive+no_connect"))
    )
    (net (code "144") (name "unconnected-(U7C-IO_L16N_T2_A27_15-PadD17)") (class "Default")
      (node (ref "U7") (pin "D17") (pinfunction "IO_L16N_T2_A27_15_D17") (pintype "passive+no_connect"))
    )
    (net (code "145") (name "unconnected-(U7C-IO_L16P_T2_A28_15-PadE17)") (class "Default")
      (node (ref "U7") (pin "E17") (pinfunction "IO_L16P_T2_A28_15_E17") (pintype "passive+no_connect"))
    )
    (net (code "146") (name "unconnected-(U7C-IO_L17N_T2_A25_15-PadJ13)") (class "Default")
      (node (ref "U7") (pin "J13") (pinfunction "IO_L17N_T2_A25_15_J13") (pintype "passive+no_connect"))
    )
    (net (code "147") (name "unconnected-(U7C-IO_L17P_T2_A26_15-PadK13)") (class "Default")
      (node (ref "U7") (pin "K13") (pinfunction "IO_L17P_T2_A26_15_K13") (pintype "passive+no_connect"))
    )
    (net (code "148") (name "unconnected-(U7C-IO_L18N_T2_A23_15-PadG17)") (class "Default")
      (node (ref "U7") (pin "G17") (pinfunction "IO_L18N_T2_A23_15_G17") (pintype "passive+no_connect"))
    )
    (net (code "149") (name "unconnected-(U7C-IO_L18P_T2_A24_15-PadH17)") (class "Default")
      (node (ref "U7") (pin "H17") (pinfunction "IO_L18P_T2_A24_15_H17") (pintype "passive+no_connect"))
    )
    (net (code "150") (name "unconnected-(U7C-IO_L19N_T3_A21_VREF_15-PadH15)") (class "Default")
      (node (ref "U7") (pin "H15") (pinfunction "IO_L19N_T3_A21_VREF_15_H15") (pintype "passive+no_connect"))
    )
    (net (code "151") (name "unconnected-(U7C-IO_L19P_T3_A22_15-PadJ14)") (class "Default")
      (node (ref "U7") (pin "J14") (pinfunction "IO_L19P_T3_A22_15_J14") (pintype "passive+no_connect"))
    )
    (net (code "152") (name "unconnected-(U7C-IO_L20N_T3_A19_15-PadC17)") (class "Default")
      (node (ref "U7") (pin "C17") (pinfunction "IO_L20N_T3_A19_15_C17") (pintype "passive+no_connect"))
    )
    (net (code "153") (name "unconnected-(U7C-IO_L20P_T3_A20_15-PadC16)") (class "Default")
      (node (ref "U7") (pin "C16") (pinfunction "IO_L20P_T3_A20_15_C16") (pintype "passive+no_connect"))
    )
    (net (code "154") (name "unconnected-(U7C-IO_L21N_T3_DQS_A18_15-PadD18)") (class "Default")
      (node (ref "U7") (pin "D18") (pinfunction "IO_L21N_T3_DQS_A18_15_D18") (pintype "passive+no_connect"))
    )
    (net (code "155") (name "unconnected-(U7C-IO_L21P_T3_DQS_15-PadE18)") (class "Default")
      (node (ref "U7") (pin "E18") (pinfunction "IO_L21P_T3_DQS_15_E18") (pintype "passive+no_connect"))
    )
    (net (code "156") (name "unconnected-(U7C-IO_L22N_T3_A16_15-PadF18)") (class "Default")
      (node (ref "U7") (pin "F18") (pinfunction "IO_L22N_T3_A16_15_F18") (pintype "passive+no_connect"))
    )
    (net (code "157") (name "unconnected-(U7C-IO_L22P_T3_A17_15-PadG18)") (class "Default")
      (node (ref "U7") (pin "G18") (pinfunction "IO_L22P_T3_A17_15_G18") (pintype "passive+no_connect"))
    )
    (net (code "158") (name "unconnected-(U7C-IO_L23N_T3_FWE_B_15-PadJ18)") (class "Default")
      (node (ref "U7") (pin "J18") (pinfunction "IO_L23N_T3_FWE_B_15_J18") (pintype "passive+no_connect"))
    )
    (net (code "159") (name "unconnected-(U7C-IO_L23P_T3_FOE_B_15-PadJ17)") (class "Default")
      (node (ref "U7") (pin "J17") (pinfunction "IO_L23P_T3_FOE_B_15_J17") (pintype "passive+no_connect"))
    )
    (net (code "160") (name "unconnected-(U7C-IO_L24N_T3_RS0_15-PadJ15)") (class "Default")
      (node (ref "U7") (pin "J15") (pinfunction "IO_L24N_T3_RS0_15_J15") (pintype "passive+no_connect"))
    )
    (net (code "161") (name "unconnected-(U7C-IO_L24P_T3_RS1_15-PadK15)") (class "Default")
      (node (ref "U7") (pin "K15") (pinfunction "IO_L24P_T3_RS1_15_K15") (pintype "passive+no_connect"))
    )
    (net (code "162") (name "unconnected-(U7D-IO_L12N_T1_MRCC_16-PadA8)") (class "Default")
      (node (ref "U7") (pin "A8") (pinfunction "IO_L12N_T1_MRCC_16_A8") (pintype "passive+no_connect"))
    )
    (net (code "163") (name "unconnected-(U7E-IO_0_34-PadK6)") (class "Default")
      (node (ref "U7") (pin "K6") (pinfunction "IO_0_34_K6") (pintype "passive+no_connect"))
    )
    (net (code "164") (name "unconnected-(U7E-IO_25_34-PadU8)") (class "Default")
      (node (ref "U7") (pin "U8") (pinfunction "IO_25_34_U8") (pintype "passive+no_connect"))
    )
    (net (code "165") (name "unconnected-(U7E-IO_L1N_T0_34-PadM1)") (class "Default")
      (node (ref "U7") (pin "M1") (pinfunction "IO_L1N_T0_34_M1") (pintype "passive+no_connect"))
    )
    (net (code "166") (name "unconnected-(U7E-IO_L1P_T0_34-PadL1)") (class "Default")
      (node (ref "U7") (pin "L1") (pinfunction "IO_L1P_T0_34_L1") (pintype "passive+no_connect"))
    )
    (net (code "167") (name "unconnected-(U7E-IO_L2N_T0_34-PadL3)") (class "Default")
      (node (ref "U7") (pin "L3") (pinfunction "IO_L2N_T0_34_L3") (pintype "passive+no_connect"))
    )
    (net (code "168") (name "unconnected-(U7E-IO_L2P_T0_34-PadK3)") (class "Default")
      (node (ref "U7") (pin "K3") (pinfunction "IO_L2P_T0_34_K3") (pintype "passive+no_connect"))
    )
    (net (code "169") (name "unconnected-(U7E-IO_L3N_T0_DQS_34-PadN1)") (class "Default")
      (node (ref "U7") (pin "N1") (pinfunction "IO_L3N_T0_DQS_34_N1") (pintype "passive+no_connect"))
    )
    (net (code "170") (name "unconnected-(U7E-IO_L3P_T0_DQS_34-PadN2)") (class "Default")
      (node (ref "U7") (pin "N2") (pinfunction "IO_L3P_T0_DQS_34_N2") (pintype "passive+no_connect"))
    )
    (net (code "171") (name "unconnected-(U7E-IO_L4N_T0_34-PadM2)") (class "Default")
      (node (ref "U7") (pin "M2") (pinfunction "IO_L4N_T0_34_M2") (pintype "passive+no_connect"))
    )
    (net (code "172") (name "unconnected-(U7E-IO_L4P_T0_34-PadM3)") (class "Default")
      (node (ref "U7") (pin "M3") (pinfunction "IO_L4P_T0_34_M3") (pintype "passive+no_connect"))
    )
    (net (code "173") (name "unconnected-(U7E-IO_L5N_T0_34-PadL4)") (class "Default")
      (node (ref "U7") (pin "L4") (pinfunction "IO_L5N_T0_34_L4") (pintype "passive+no_connect"))
    )
    (net (code "174") (name "unconnected-(U7E-IO_L5P_T0_34-PadK5)") (class "Default")
      (node (ref "U7") (pin "K5") (pinfunction "IO_L5P_T0_34_K5") (pintype "passive+no_connect"))
    )
    (net (code "175") (name "unconnected-(U7E-IO_L6N_T0_VREF_34-PadL5)") (class "Default")
      (node (ref "U7") (pin "L5") (pinfunction "IO_L6N_T0_VREF_34_L5") (pintype "passive+no_connect"))
    )
    (net (code "176") (name "unconnected-(U7E-IO_L6P_T0_34-PadL6)") (class "Default")
      (node (ref "U7") (pin "L6") (pinfunction "IO_L6P_T0_34_L6") (pintype "passive+no_connect"))
    )
    (net (code "177") (name "unconnected-(U7E-IO_L7N_T1_34-PadV1)") (class "Default")
      (node (ref "U7") (pin "V1") (pinfunction "IO_L7N_T1_34_V1") (pintype "passive+no_connect"))
    )
    (net (code "178") (name "unconnected-(U7E-IO_L7P_T1_34-PadU1)") (class "Default")
      (node (ref "U7") (pin "U1") (pinfunction "IO_L7P_T1_34_U1") (pintype "passive+no_connect"))
    )
    (net (code "179") (name "unconnected-(U7E-IO_L8N_T1_34-PadU3)") (class "Default")
      (node (ref "U7") (pin "U3") (pinfunction "IO_L8N_T1_34_U3") (pintype "passive+no_connect"))
    )
    (net (code "180") (name "unconnected-(U7E-IO_L8P_T1_34-PadU4)") (class "Default")
      (node (ref "U7") (pin "U4") (pinfunction "IO_L8P_T1_34_U4") (pintype "passive+no_connect"))
    )
    (net (code "181") (name "unconnected-(U7E-IO_L9N_T1_DQS_34-PadV2)") (class "Default")
      (node (ref "U7") (pin "V2") (pinfunction "IO_L9N_T1_DQS_34_V2") (pintype "passive+no_connect"))
    )
    (net (code "182") (name "unconnected-(U7E-IO_L9P_T1_DQS_34-PadU2)") (class "Default")
      (node (ref "U7") (pin "U2") (pinfunction "IO_L9P_T1_DQS_34_U2") (pintype "passive+no_connect"))
    )
    (net (code "183") (name "unconnected-(U7E-IO_L10N_T1_34-PadV4)") (class "Default")
      (node (ref "U7") (pin "V4") (pinfunction "IO_L10N_T1_34_V4") (pintype "passive+no_connect"))
    )
    (net (code "184") (name "unconnected-(U7E-IO_L10P_T1_34-PadV5)") (class "Default")
      (node (ref "U7") (pin "V5") (pinfunction "IO_L10P_T1_34_V5") (pintype "passive+no_connect"))
    )
    (net (code "185") (name "unconnected-(U7E-IO_L11N_T1_SRCC_34-PadT3)") (class "Default")
      (node (ref "U7") (pin "T3") (pinfunction "IO_L11N_T1_SRCC_34_T3") (pintype "passive+no_connect"))
    )
    (net (code "186") (name "unconnected-(U7E-IO_L11P_T1_SRCC_34-PadR3)") (class "Default")
      (node (ref "U7") (pin "R3") (pinfunction "IO_L11P_T1_SRCC_34_R3") (pintype "passive+no_connect"))
    )
    (net (code "187") (name "unconnected-(U7E-IO_L12N_T1_MRCC_34-PadT4)") (class "Default")
      (node (ref "U7") (pin "T4") (pinfunction "IO_L12N_T1_MRCC_34_T4") (pintype "passive+no_connect"))
    )
    (net (code "188") (name "unconnected-(U7E-IO_L12P_T1_MRCC_34-PadT5)") (class "Default")
      (node (ref "U7") (pin "T5") (pinfunction "IO_L12P_T1_MRCC_34_T5") (pintype "passive+no_connect"))
    )
    (net (code "189") (name "unconnected-(U7E-IO_L13N_T2_MRCC_34-PadP5)") (class "Default")
      (node (ref "U7") (pin "P5") (pinfunction "IO_L13N_T2_MRCC_34_P5") (pintype "passive+no_connect"))
    )
    (net (code "190") (name "unconnected-(U7E-IO_L13P_T2_MRCC_34-PadN5)") (class "Default")
      (node (ref "U7") (pin "N5") (pinfunction "IO_L13P_T2_MRCC_34_N5") (pintype "passive+no_connect"))
    )
    (net (code "191") (name "unconnected-(U7E-IO_L14N_T2_SRCC_34-PadP3)") (class "Default")
      (node (ref "U7") (pin "P3") (pinfunction "IO_L14N_T2_SRCC_34_P3") (pintype "passive+no_connect"))
    )
    (net (code "192") (name "unconnected-(U7E-IO_L14P_T2_SRCC_34-PadP4)") (class "Default")
      (node (ref "U7") (pin "P4") (pinfunction "IO_L14P_T2_SRCC_34_P4") (pintype "passive+no_connect"))
    )
    (net (code "193") (name "unconnected-(U7E-IO_L15N_T2_DQS_34-PadR2)") (class "Default")
      (node (ref "U7") (pin "R2") (pinfunction "IO_L15N_T2_DQS_34_R2") (pintype "passive+no_connect"))
    )
    (net (code "194") (name "unconnected-(U7E-IO_L15P_T2_DQS_34-PadP2)") (class "Default")
      (node (ref "U7") (pin "P2") (pinfunction "IO_L15P_T2_DQS_34_P2") (pintype "passive+no_connect"))
    )
    (net (code "195") (name "unconnected-(U7E-IO_L16N_T2_34-PadN4)") (class "Default")
      (node (ref "U7") (pin "N4") (pinfunction "IO_L16N_T2_34_N4") (pintype "passive+no_connect"))
    )
    (net (code "196") (name "unconnected-(U7E-IO_L16P_T2_34-PadM4)") (class "Default")
      (node (ref "U7") (pin "M4") (pinfunction "IO_L16P_T2_34_M4") (pintype "passive+no_connect"))
    )
    (net (code "197") (name "unconnected-(U7E-IO_L17N_T2_34-PadT1)") (class "Default")
      (node (ref "U7") (pin "T1") (pinfunction "IO_L17N_T2_34_T1") (pintype "passive+no_connect"))
    )
    (net (code "198") (name "unconnected-(U7E-IO_L17P_T2_34-PadR1)") (class "Default")
      (node (ref "U7") (pin "R1") (pinfunction "IO_L17P_T2_34_R1") (pintype "passive+no_connect"))
    )
    (net (code "199") (name "unconnected-(U7E-IO_L18N_T2_34-PadN6)") (class "Default")
      (node (ref "U7") (pin "N6") (pinfunction "IO_L18N_T2_34_N6") (pintype "passive+no_connect"))
    )
    (net (code "200") (name "unconnected-(U7E-IO_L18P_T2_34-PadM6)") (class "Default")
      (node (ref "U7") (pin "M6") (pinfunction "IO_L18P_T2_34_M6") (pintype "passive+no_connect"))
    )
    (net (code "201") (name "unconnected-(U7E-IO_L19N_T3_VREF_34-PadR5)") (class "Default")
      (node (ref "U7") (pin "R5") (pinfunction "IO_L19N_T3_VREF_34_R5") (pintype "passive+no_connect"))
    )
    (net (code "202") (name "unconnected-(U7E-IO_L19P_T3_34-PadR6)") (class "Default")
      (node (ref "U7") (pin "R6") (pinfunction "IO_L19P_T3_34_R6") (pintype "passive+no_connect"))
    )
    (net (code "203") (name "unconnected-(U7E-IO_L20N_T3_34-PadV6)") (class "Default")
      (node (ref "U7") (pin "V6") (pinfunction "IO_L20N_T3_34_V6") (pintype "passive+no_connect"))
    )
    (net (code "204") (name "unconnected-(U7E-IO_L20P_T3_34-PadV7)") (class "Default")
      (node (ref "U7") (pin "V7") (pinfunction "IO_L20P_T3_34_V7") (pintype "passive+no_connect"))
    )
    (net (code "205") (name "unconnected-(U7E-IO_L21N_T3_DQS_34-PadV9)") (class "Default")
      (node (ref "U7") (pin "V9") (pinfunction "IO_L21N_T3_DQS_34_V9") (pintype "passive+no_connect"))
    )
    (net (code "206") (name "unconnected-(U7E-IO_L21P_T3_DQS_34-PadU9)") (class "Default")
      (node (ref "U7") (pin "U9") (pinfunction "IO_L21P_T3_DQS_34_U9") (pintype "passive+no_connect"))
    )
    (net (code "207") (name "unconnected-(U7E-IO_L22N_T3_34-PadU6)") (class "Default")
      (node (ref "U7") (pin "U6") (pinfunction "IO_L22N_T3_34_U6") (pintype "passive+no_connect"))
    )
    (net (code "208") (name "unconnected-(U7E-IO_L22P_T3_34-PadU7)") (class "Default")
      (node (ref "U7") (pin "U7") (pinfunction "IO_L22P_T3_34_U7") (pintype "passive+no_connect"))
    )
    (net (code "209") (name "unconnected-(U7E-IO_L23N_T3_34-PadT6)") (class "Default")
      (node (ref "U7") (pin "T6") (pinfunction "IO_L23N_T3_34_T6") (pintype "passive+no_connect"))
    )
    (net (code "210") (name "unconnected-(U7E-IO_L23P_T3_34-PadR7)") (class "Default")
      (node (ref "U7") (pin "R7") (pinfunction "IO_L23P_T3_34_R7") (pintype "passive+no_connect"))
    )
    (net (code "211") (name "unconnected-(U7E-IO_L24N_T3_34-PadT8)") (class "Default")
      (node (ref "U7") (pin "T8") (pinfunction "IO_L24N_T3_34_T8") (pintype "passive+no_connect"))
    )
    (net (code "212") (name "unconnected-(U7E-IO_L24P_T3_34-PadR8)") (class "Default")
      (node (ref "U7") (pin "R8") (pinfunction "IO_L24P_T3_34_R8") (pintype "passive+no_connect"))
    )
    (net (code "213") (name "unconnected-(U7F-IO_25_35-PadJ5)") (class "Default")
      (node (ref "U7") (pin "J5") (pinfunction "IO_25_35_J5") (pintype "passive+no_connect"))
    )
    (net (code "214") (name "unconnected-(U7F-IO_L24N_T3_35-PadH5)") (class "Default")
      (node (ref "U7") (pin "H5") (pinfunction "IO_L24N_T3_35_H5") (pintype "passive+no_connect"))
    )
  )
)
